# main_board.net
KiCad netlist of a schematic drawn in EAGLE
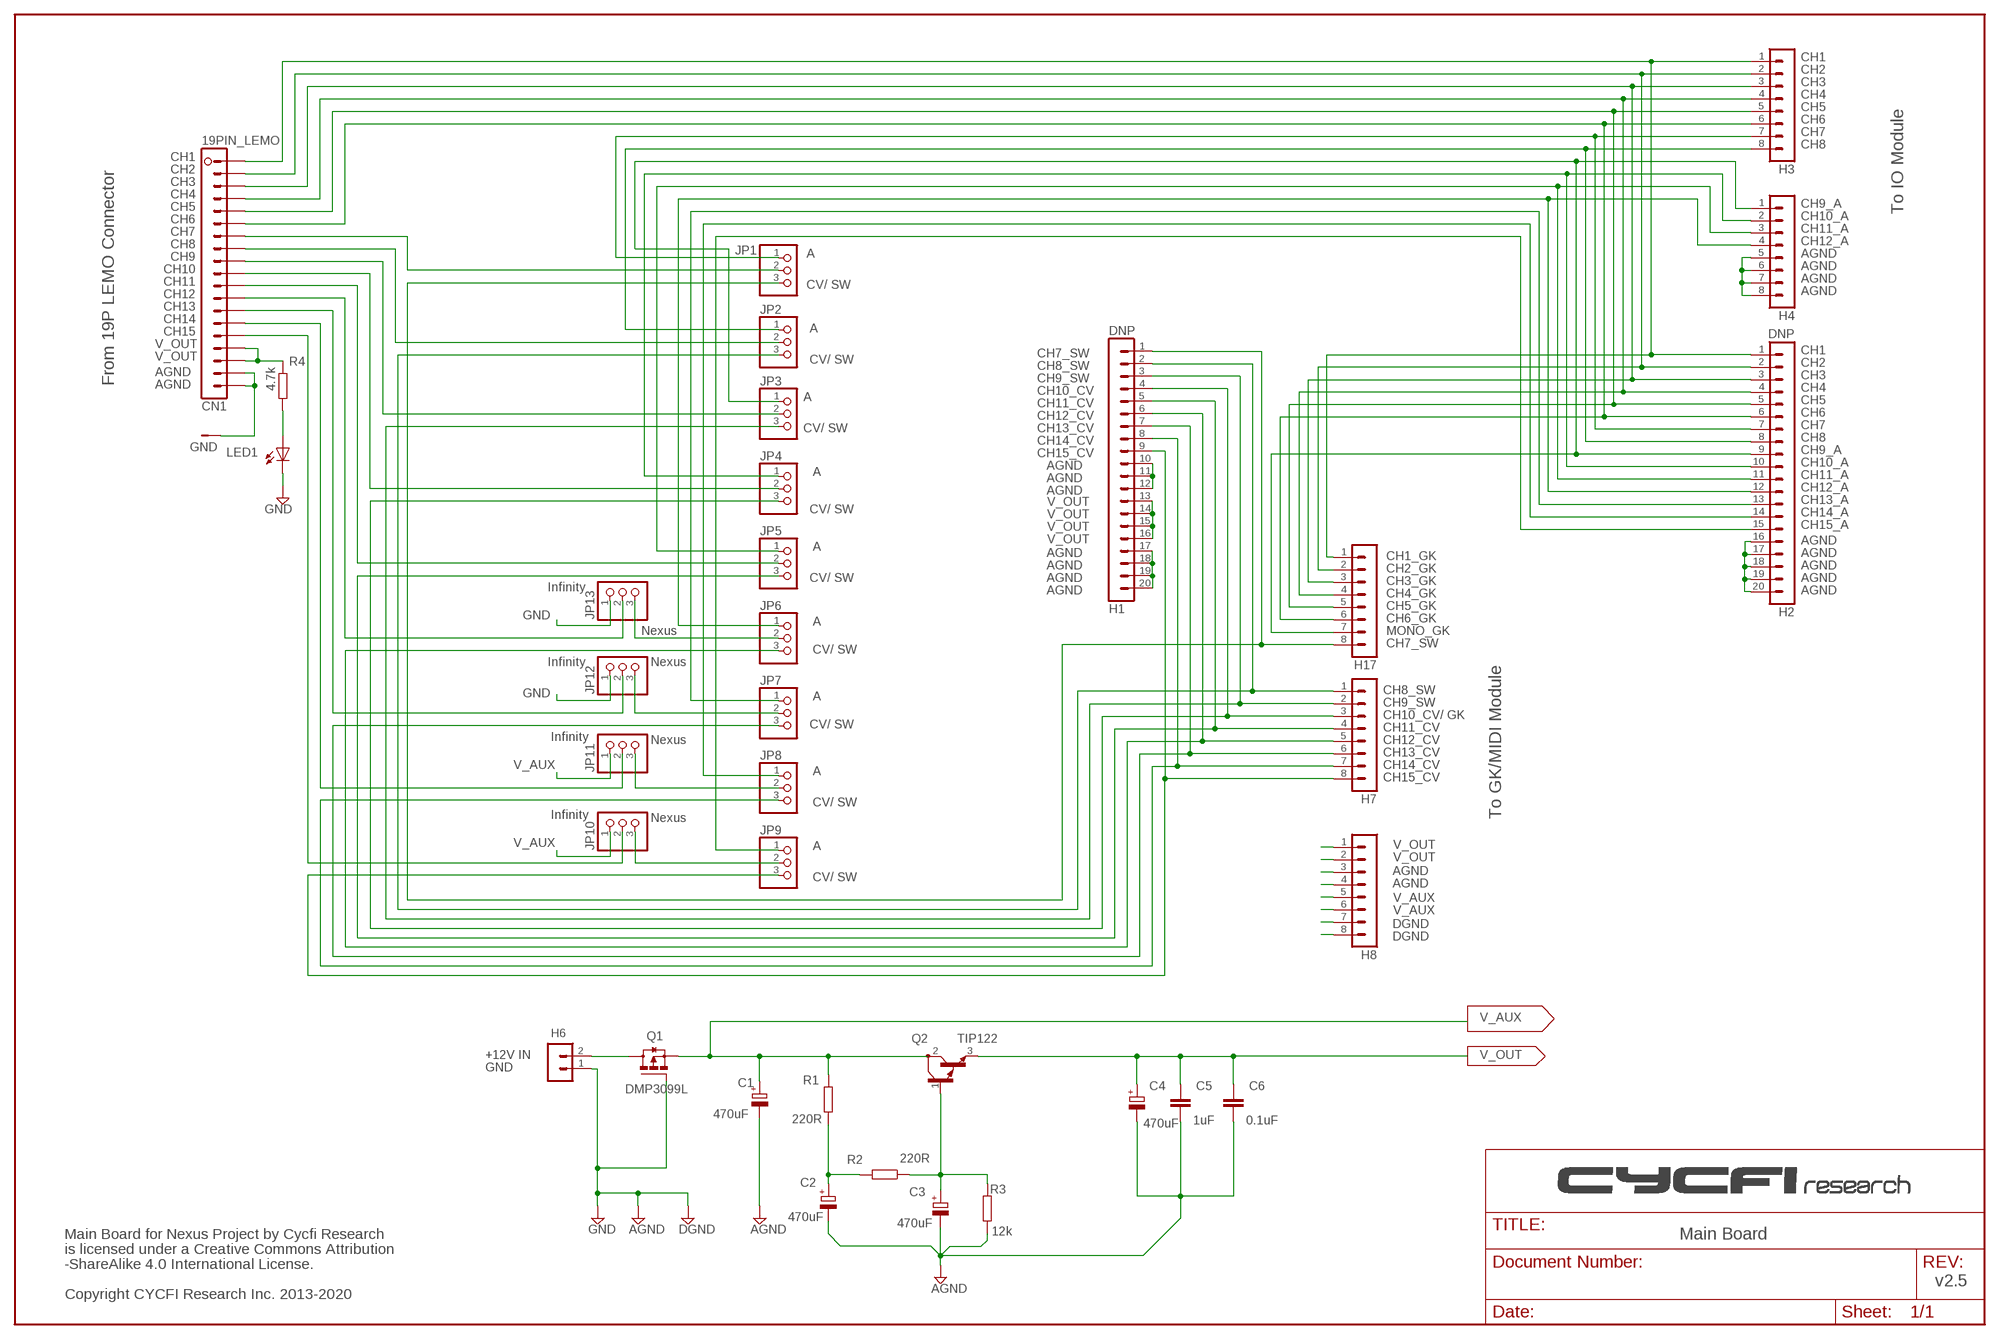
[diagram p0: schematic, sheet 1]

(export (version "E")
  (design (tool "Eeschema 10.0.6"))
  (components
    (comp (ref "C1")
      (value "470uF")
      (footprint "eagle-import:140CLH-1010")
      (libsource (lib "eagle-import") (part "CPOL-EU140CLH-1010"))
    )
    (comp (ref "C2")
      (value "470uF")
      (footprint "eagle-import:140CLH-1010")
      (libsource (lib "eagle-import") (part "CPOL-EU140CLH-1010"))
    )
    (comp (ref "C3")
      (value "470uF")
      (footprint "eagle-import:140CLH-1010")
      (libsource (lib "eagle-import") (part "CPOL-EU140CLH-1010"))
    )
    (comp (ref "C4")
      (value "470uF")
      (footprint "eagle-import:140CLH-1010")
      (libsource (lib "eagle-import") (part "CPOL-EU140CLH-1010"))
    )
    (comp (ref "C5")
      (value "1uF")
      (footprint "eagle-import:C0603")
      (libsource (lib "eagle-import") (part "C-EUC0603"))
    )
    (comp (ref "C6")
      (value "0.1uF")
      (footprint "eagle-import:C0603")
      (libsource (lib "eagle-import") (part "C-EUC0603"))
    )
    (comp (ref "CN1")
      (value "19PIN_LEMO")
      (footprint "eagle-import:19PIN_LEMO")
      (libsource (lib "eagle-import") (part "19PIN_LEMO"))
    )
    (comp (ref "GND")
      (value "TH-PAD-1.6/0.8")
      (footprint "eagle-import:TH-PAD-1.6_0.8")
      (libsource (lib "eagle-import") (part "TH-PAD-1.6/0.8"))
    )
    (comp (ref "H1")
      (value "DNP")
      (footprint "eagle-import:MA20-1")
      (libsource (lib "eagle-import") (part "MA20-1"))
    )
    (comp (ref "H2")
      (value "DNP")
      (footprint "eagle-import:MA20-1")
      (libsource (lib "eagle-import") (part "MA20-1"))
    )
    (comp (ref "H3")
      (value "MA08-1")
      (footprint "eagle-import:MA08-1")
      (libsource (lib "eagle-import") (part "MA08-1"))
    )
    (comp (ref "H4")
      (value "MA08-1")
      (footprint "eagle-import:MA08-1")
      (libsource (lib "eagle-import") (part "MA08-1"))
    )
    (comp (ref "H6")
      (value "MA02-1")
      (footprint "eagle-import:MA02-1")
      (libsource (lib "eagle-import") (part "MA02-1"))
    )
    (comp (ref "H7")
      (value "MA08-1")
      (footprint "eagle-import:MA08-1")
      (libsource (lib "eagle-import") (part "MA08-1"))
    )
    (comp (ref "H8")
      (value "MA08-1")
      (footprint "eagle-import:MA08-1")
      (libsource (lib "eagle-import") (part "MA08-1"))
    )
    (comp (ref "H17")
      (value "MA08-1")
      (footprint "eagle-import:MA08-1")
      (libsource (lib "eagle-import") (part "MA08-1"))
    )
    (comp (ref "JP1")
      (value "PINHD-1X03_2.00")
      (footprint "eagle-import:1X03M")
      (libsource (lib "eagle-import") (part "PINHD-1X03_2.00"))
    )
    (comp (ref "JP2")
      (value "PINHD-1X03_2.00")
      (footprint "eagle-import:1X03M")
      (libsource (lib "eagle-import") (part "PINHD-1X03_2.00"))
    )
    (comp (ref "JP3")
      (value "PINHD-1X03_2.00")
      (footprint "eagle-import:1X03M")
      (libsource (lib "eagle-import") (part "PINHD-1X03_2.00"))
    )
    (comp (ref "JP4")
      (value "PINHD-1X03_2.00")
      (footprint "eagle-import:1X03M")
      (libsource (lib "eagle-import") (part "PINHD-1X03_2.00"))
    )
    (comp (ref "JP5")
      (value "PINHD-1X03_2.00")
      (footprint "eagle-import:1X03M")
      (libsource (lib "eagle-import") (part "PINHD-1X03_2.00"))
    )
    (comp (ref "JP6")
      (value "PINHD-1X03_2.00")
      (footprint "eagle-import:1X03M")
      (libsource (lib "eagle-import") (part "PINHD-1X03_2.00"))
    )
    (comp (ref "JP7")
      (value "PINHD-1X03_2.00")
      (footprint "eagle-import:1X03M")
      (libsource (lib "eagle-import") (part "PINHD-1X03_2.00"))
    )
    (comp (ref "JP8")
      (value "PINHD-1X03_2.00")
      (footprint "eagle-import:1X03M")
      (libsource (lib "eagle-import") (part "PINHD-1X03_2.00"))
    )
    (comp (ref "JP9")
      (value "PINHD-1X03_2.00")
      (footprint "eagle-import:1X03M")
      (libsource (lib "eagle-import") (part "PINHD-1X03_2.00"))
    )
    (comp (ref "JP10")
      (value "PINHD-1X03_2.00")
      (footprint "eagle-import:1X03M")
      (libsource (lib "eagle-import") (part "PINHD-1X03_2.00"))
    )
    (comp (ref "JP11")
      (value "PINHD-1X03_2.00")
      (footprint "eagle-import:1X03M")
      (libsource (lib "eagle-import") (part "PINHD-1X03_2.00"))
    )
    (comp (ref "JP12")
      (value "PINHD-1X03_2.00")
      (footprint "eagle-import:1X03M")
      (libsource (lib "eagle-import") (part "PINHD-1X03_2.00"))
    )
    (comp (ref "JP13")
      (value "PINHD-1X03_2.00")
      (footprint "eagle-import:1X03M")
      (libsource (lib "eagle-import") (part "PINHD-1X03_2.00"))
    )
    (comp (ref "LED1")
      (value "LED3MM")
      (footprint "eagle-import:LED3MM")
      (libsource (lib "eagle-import") (part "LED3MM"))
    )
    (comp (ref "Q1")
      (value "DMP3099L")
      (footprint "eagle-import:SOT23")
      (libsource (lib "eagle-import") (part "P_MOSFET"))
    )
    (comp (ref "Q2")
      (value "TIP122")
      (footprint "eagle-import:TO-220H")
      (libsource (lib "eagle-import") (part "TIP122"))
    )
    (comp (ref "R1")
      (value "220R")
      (footprint "eagle-import:R0603")
      (libsource (lib "eagle-import") (part "R-EU_R0603"))
    )
    (comp (ref "R2")
      (value "220R")
      (footprint "eagle-import:R0603")
      (libsource (lib "eagle-import") (part "R-EU_R0603"))
    )
    (comp (ref "R3")
      (value "12k")
      (footprint "eagle-import:R0603")
      (libsource (lib "eagle-import") (part "R-EU_R0603"))
    )
    (comp (ref "R4")
      (value "4.7k")
      (footprint "eagle-import:R0402")
      (libsource (lib "eagle-import") (part "R-EU_R0402"))
    )
  )
  (nets
    (net (code "1") (name "/V_AUX") (class "Default")
      (node (ref "C1") (pin "+") (pinfunction "+_+") (pintype "passive"))
      (node (ref "H8") (pin "5") (pinfunction "5_5") (pintype "passive"))
      (node (ref "H8") (pin "6") (pinfunction "6_6") (pintype "passive"))
      (node (ref "JP10") (pin "1") (pinfunction "1_1") (pintype "passive"))
      (node (ref "JP11") (pin "1") (pinfunction "1_1") (pintype "passive"))
      (node (ref "Q1") (pin "2") (pinfunction "S_2") (pintype "passive"))
      (node (ref "Q2") (pin "2") (pinfunction "C_2") (pintype "passive"))
      (node (ref "R1") (pin "2") (pinfunction "2_2") (pintype "passive"))
    )
    (net (code "2") (name "/V_OUT") (class "Default")
      (node (ref "C4") (pin "+") (pinfunction "+_+") (pintype "passive"))
      (node (ref "C5") (pin "1") (pinfunction "1_1") (pintype "passive"))
      (node (ref "C6") (pin "1") (pinfunction "1_1") (pintype "passive"))
      (node (ref "CN1") (pin "P$16") (pinfunction "16_P$16") (pintype "passive"))
      (node (ref "CN1") (pin "P$17") (pinfunction "17_P$17") (pintype "passive"))
      (node (ref "H1") (pin "13") (pinfunction "13_13") (pintype "passive"))
      (node (ref "H1") (pin "14") (pinfunction "14_14") (pintype "passive"))
      (node (ref "H1") (pin "15") (pinfunction "15_15") (pintype "passive"))
      (node (ref "H1") (pin "16") (pinfunction "16_16") (pintype "passive"))
      (node (ref "H8") (pin "1") (pinfunction "1_1") (pintype "passive"))
      (node (ref "H8") (pin "2") (pinfunction "2_2") (pintype "passive"))
      (node (ref "Q2") (pin "3") (pinfunction "E_3") (pintype "passive"))
      (node (ref "R4") (pin "1") (pinfunction "1_1") (pintype "passive"))
    )
    (net (code "3") (name "AGND") (class "Default")
      (node (ref "C1") (pin "-") (pinfunction "-_-") (pintype "passive"))
      (node (ref "C2") (pin "-") (pinfunction "-_-") (pintype "passive"))
      (node (ref "C3") (pin "-") (pinfunction "-_-") (pintype "passive"))
      (node (ref "C4") (pin "-") (pinfunction "-_-") (pintype "passive"))
      (node (ref "C5") (pin "2") (pinfunction "2_2") (pintype "passive"))
      (node (ref "C6") (pin "2") (pinfunction "2_2") (pintype "passive"))
      (node (ref "CN1") (pin "P$18") (pinfunction "18_P$18") (pintype "passive"))
      (node (ref "CN1") (pin "P$19") (pinfunction "19_P$19") (pintype "passive"))
      (node (ref "GND") (pin "1") (pinfunction "P_1") (pintype "passive"))
      (node (ref "H1") (pin "10") (pinfunction "10_10") (pintype "passive"))
      (node (ref "H1") (pin "11") (pinfunction "11_11") (pintype "passive"))
      (node (ref "H1") (pin "12") (pinfunction "12_12") (pintype "passive"))
      (node (ref "H1") (pin "17") (pinfunction "17_17") (pintype "passive"))
      (node (ref "H1") (pin "18") (pinfunction "18_18") (pintype "passive"))
      (node (ref "H1") (pin "19") (pinfunction "19_19") (pintype "passive"))
      (node (ref "H1") (pin "20") (pinfunction "20_20") (pintype "passive"))
      (node (ref "H2") (pin "16") (pinfunction "16_16") (pintype "passive"))
      (node (ref "H2") (pin "17") (pinfunction "17_17") (pintype "passive"))
      (node (ref "H2") (pin "18") (pinfunction "18_18") (pintype "passive"))
      (node (ref "H2") (pin "19") (pinfunction "19_19") (pintype "passive"))
      (node (ref "H2") (pin "20") (pinfunction "20_20") (pintype "passive"))
      (node (ref "H4") (pin "5") (pinfunction "5_5") (pintype "passive"))
      (node (ref "H4") (pin "6") (pinfunction "6_6") (pintype "passive"))
      (node (ref "H4") (pin "7") (pinfunction "7_7") (pintype "passive"))
      (node (ref "H4") (pin "8") (pinfunction "8_8") (pintype "passive"))
      (node (ref "H6") (pin "1") (pinfunction "1_1") (pintype "passive"))
      (node (ref "H8") (pin "3") (pinfunction "3_3") (pintype "passive"))
      (node (ref "H8") (pin "4") (pinfunction "4_4") (pintype "passive"))
      (node (ref "H8") (pin "7") (pinfunction "7_7") (pintype "passive"))
      (node (ref "H8") (pin "8") (pinfunction "8_8") (pintype "passive"))
      (node (ref "JP12") (pin "1") (pinfunction "1_1") (pintype "passive"))
      (node (ref "JP13") (pin "1") (pinfunction "1_1") (pintype "passive"))
      (node (ref "LED1") (pin "K") (pinfunction "C_K") (pintype "passive"))
      (node (ref "Q1") (pin "1") (pinfunction "G_1") (pintype "passive"))
      (node (ref "R3") (pin "1") (pinfunction "1_1") (pintype "passive"))
    )
    (net (code "4") (name "Net-(C2-Pad+)") (class "Default")
      (node (ref "C2") (pin "+") (pinfunction "+_+") (pintype "passive"))
      (node (ref "R1") (pin "1") (pinfunction "1_1") (pintype "passive"))
      (node (ref "R2") (pin "2") (pinfunction "2_2") (pintype "passive"))
    )
    (net (code "5") (name "Net-(CN1-1)") (class "Default")
      (node (ref "CN1") (pin "P$1") (pinfunction "1_P$1") (pintype "passive"))
      (node (ref "H17") (pin "1") (pinfunction "1_1") (pintype "passive"))
      (node (ref "H2") (pin "1") (pinfunction "1_1") (pintype "passive"))
      (node (ref "H3") (pin "1") (pinfunction "1_1") (pintype "passive"))
    )
    (net (code "6") (name "Net-(CN1-2)") (class "Default")
      (node (ref "CN1") (pin "P$2") (pinfunction "2_P$2") (pintype "passive"))
      (node (ref "H17") (pin "2") (pinfunction "2_2") (pintype "passive"))
      (node (ref "H2") (pin "2") (pinfunction "2_2") (pintype "passive"))
      (node (ref "H3") (pin "2") (pinfunction "2_2") (pintype "passive"))
    )
    (net (code "7") (name "Net-(CN1-3)") (class "Default")
      (node (ref "CN1") (pin "P$3") (pinfunction "3_P$3") (pintype "passive"))
      (node (ref "H17") (pin "3") (pinfunction "3_3") (pintype "passive"))
      (node (ref "H2") (pin "3") (pinfunction "3_3") (pintype "passive"))
      (node (ref "H3") (pin "3") (pinfunction "3_3") (pintype "passive"))
    )
    (net (code "8") (name "Net-(CN1-4)") (class "Default")
      (node (ref "CN1") (pin "P$4") (pinfunction "4_P$4") (pintype "passive"))
      (node (ref "H17") (pin "4") (pinfunction "4_4") (pintype "passive"))
      (node (ref "H2") (pin "4") (pinfunction "4_4") (pintype "passive"))
      (node (ref "H3") (pin "4") (pinfunction "4_4") (pintype "passive"))
    )
    (net (code "9") (name "Net-(CN1-5)") (class "Default")
      (node (ref "CN1") (pin "P$5") (pinfunction "5_P$5") (pintype "passive"))
      (node (ref "H17") (pin "5") (pinfunction "5_5") (pintype "passive"))
      (node (ref "H2") (pin "5") (pinfunction "5_5") (pintype "passive"))
      (node (ref "H3") (pin "5") (pinfunction "5_5") (pintype "passive"))
    )
    (net (code "10") (name "Net-(CN1-6)") (class "Default")
      (node (ref "CN1") (pin "P$6") (pinfunction "6_P$6") (pintype "passive"))
      (node (ref "H17") (pin "6") (pinfunction "6_6") (pintype "passive"))
      (node (ref "H2") (pin "6") (pinfunction "6_6") (pintype "passive"))
      (node (ref "H3") (pin "6") (pinfunction "6_6") (pintype "passive"))
    )
    (net (code "11") (name "Net-(CN1-7)") (class "Default")
      (node (ref "CN1") (pin "P$7") (pinfunction "7_P$7") (pintype "passive"))
      (node (ref "JP1") (pin "2") (pinfunction "2_2") (pintype "passive"))
    )
    (net (code "12") (name "Net-(CN1-8)") (class "Default")
      (node (ref "CN1") (pin "P$8") (pinfunction "8_P$8") (pintype "passive"))
      (node (ref "JP2") (pin "2") (pinfunction "2_2") (pintype "passive"))
    )
    (net (code "13") (name "Net-(CN1-9)") (class "Default")
      (node (ref "CN1") (pin "P$9") (pinfunction "9_P$9") (pintype "passive"))
      (node (ref "JP3") (pin "2") (pinfunction "2_2") (pintype "passive"))
    )
    (net (code "14") (name "Net-(CN1-10)") (class "Default")
      (node (ref "CN1") (pin "P$10") (pinfunction "10_P$10") (pintype "passive"))
      (node (ref "JP4") (pin "2") (pinfunction "2_2") (pintype "passive"))
    )
    (net (code "15") (name "Net-(CN1-11)") (class "Default")
      (node (ref "CN1") (pin "P$11") (pinfunction "11_P$11") (pintype "passive"))
      (node (ref "JP5") (pin "2") (pinfunction "2_2") (pintype "passive"))
    )
    (net (code "16") (name "Net-(CN1-12)") (class "Default")
      (node (ref "CN1") (pin "P$12") (pinfunction "12_P$12") (pintype "passive"))
      (node (ref "JP13") (pin "2") (pinfunction "2_2") (pintype "passive"))
    )
    (net (code "17") (name "Net-(CN1-13)") (class "Default")
      (node (ref "CN1") (pin "P$13") (pinfunction "13_P$13") (pintype "passive"))
      (node (ref "JP12") (pin "2") (pinfunction "2_2") (pintype "passive"))
    )
    (net (code "18") (name "Net-(CN1-14)") (class "Default")
      (node (ref "CN1") (pin "P$14") (pinfunction "14_P$14") (pintype "passive"))
      (node (ref "JP11") (pin "2") (pinfunction "2_2") (pintype "passive"))
    )
    (net (code "19") (name "Net-(CN1-15)") (class "Default")
      (node (ref "CN1") (pin "P$15") (pinfunction "15_P$15") (pintype "passive"))
      (node (ref "JP10") (pin "2") (pinfunction "2_2") (pintype "passive"))
    )
    (net (code "20") (name "Net-(H1-Pad1)") (class "Default")
      (node (ref "H1") (pin "1") (pinfunction "1_1") (pintype "passive"))
      (node (ref "H17") (pin "8") (pinfunction "8_8") (pintype "passive"))
      (node (ref "JP1") (pin "3") (pinfunction "3_3") (pintype "passive"))
    )
    (net (code "21") (name "Net-(H1-Pad2)") (class "Default")
      (node (ref "H1") (pin "2") (pinfunction "2_2") (pintype "passive"))
      (node (ref "H7") (pin "1") (pinfunction "1_1") (pintype "passive"))
      (node (ref "JP2") (pin "3") (pinfunction "3_3") (pintype "passive"))
    )
    (net (code "22") (name "Net-(H1-Pad3)") (class "Default")
      (node (ref "H1") (pin "3") (pinfunction "3_3") (pintype "passive"))
      (node (ref "H7") (pin "2") (pinfunction "2_2") (pintype "passive"))
      (node (ref "JP3") (pin "3") (pinfunction "3_3") (pintype "passive"))
    )
    (net (code "23") (name "Net-(H1-Pad4)") (class "Default")
      (node (ref "H1") (pin "4") (pinfunction "4_4") (pintype "passive"))
      (node (ref "H7") (pin "3") (pinfunction "3_3") (pintype "passive"))
      (node (ref "JP4") (pin "3") (pinfunction "3_3") (pintype "passive"))
    )
    (net (code "24") (name "Net-(H1-Pad5)") (class "Default")
      (node (ref "H1") (pin "5") (pinfunction "5_5") (pintype "passive"))
      (node (ref "H7") (pin "4") (pinfunction "4_4") (pintype "passive"))
      (node (ref "JP5") (pin "3") (pinfunction "3_3") (pintype "passive"))
    )
    (net (code "25") (name "Net-(H1-Pad6)") (class "Default")
      (node (ref "H1") (pin "6") (pinfunction "6_6") (pintype "passive"))
      (node (ref "H7") (pin "5") (pinfunction "5_5") (pintype "passive"))
      (node (ref "JP6") (pin "3") (pinfunction "3_3") (pintype "passive"))
    )
    (net (code "26") (name "Net-(H1-Pad7)") (class "Default")
      (node (ref "H1") (pin "7") (pinfunction "7_7") (pintype "passive"))
      (node (ref "H7") (pin "6") (pinfunction "6_6") (pintype "passive"))
      (node (ref "JP7") (pin "3") (pinfunction "3_3") (pintype "passive"))
    )
    (net (code "27") (name "Net-(H1-Pad8)") (class "Default")
      (node (ref "H1") (pin "8") (pinfunction "8_8") (pintype "passive"))
      (node (ref "H7") (pin "7") (pinfunction "7_7") (pintype "passive"))
      (node (ref "JP8") (pin "3") (pinfunction "3_3") (pintype "passive"))
    )
    (net (code "28") (name "Net-(H1-Pad9)") (class "Default")
      (node (ref "H1") (pin "9") (pinfunction "9_9") (pintype "passive"))
      (node (ref "H7") (pin "8") (pinfunction "8_8") (pintype "passive"))
      (node (ref "JP9") (pin "3") (pinfunction "3_3") (pintype "passive"))
    )
    (net (code "29") (name "Net-(H2-Pad7)") (class "Default")
      (node (ref "H2") (pin "7") (pinfunction "7_7") (pintype "passive"))
      (node (ref "H3") (pin "7") (pinfunction "7_7") (pintype "passive"))
      (node (ref "JP1") (pin "1") (pinfunction "1_1") (pintype "passive"))
    )
    (net (code "30") (name "Net-(H2-Pad8)") (class "Default")
      (node (ref "H2") (pin "8") (pinfunction "8_8") (pintype "passive"))
      (node (ref "H3") (pin "8") (pinfunction "8_8") (pintype "passive"))
      (node (ref "JP2") (pin "1") (pinfunction "1_1") (pintype "passive"))
    )
    (net (code "31") (name "Net-(H2-Pad10)") (class "Default")
      (node (ref "H2") (pin "10") (pinfunction "10_10") (pintype "passive"))
      (node (ref "H4") (pin "2") (pinfunction "2_2") (pintype "passive"))
      (node (ref "JP4") (pin "1") (pinfunction "1_1") (pintype "passive"))
    )
    (net (code "32") (name "Net-(H2-Pad11)") (class "Default")
      (node (ref "H2") (pin "11") (pinfunction "11_11") (pintype "passive"))
      (node (ref "H4") (pin "3") (pinfunction "3_3") (pintype "passive"))
      (node (ref "JP5") (pin "1") (pinfunction "1_1") (pintype "passive"))
    )
    (net (code "33") (name "Net-(H2-Pad12)") (class "Default")
      (node (ref "H2") (pin "12") (pinfunction "12_12") (pintype "passive"))
      (node (ref "H4") (pin "4") (pinfunction "4_4") (pintype "passive"))
      (node (ref "JP6") (pin "1") (pinfunction "1_1") (pintype "passive"))
    )
    (net (code "34") (name "Net-(H2-Pad13)") (class "Default")
      (node (ref "H2") (pin "13") (pinfunction "13_13") (pintype "passive"))
      (node (ref "JP7") (pin "1") (pinfunction "1_1") (pintype "passive"))
    )
    (net (code "35") (name "Net-(H2-Pad14)") (class "Default")
      (node (ref "H2") (pin "14") (pinfunction "14_14") (pintype "passive"))
      (node (ref "JP8") (pin "1") (pinfunction "1_1") (pintype "passive"))
    )
    (net (code "36") (name "Net-(H2-Pad15)") (class "Default")
      (node (ref "H2") (pin "15") (pinfunction "15_15") (pintype "passive"))
      (node (ref "JP9") (pin "1") (pinfunction "1_1") (pintype "passive"))
    )
    (net (code "37") (name "Net-(H17-Pad7)") (class "Default")
      (node (ref "H17") (pin "7") (pinfunction "7_7") (pintype "passive"))
      (node (ref "H2") (pin "9") (pinfunction "9_9") (pintype "passive"))
      (node (ref "H4") (pin "1") (pinfunction "1_1") (pintype "passive"))
      (node (ref "JP3") (pin "1") (pinfunction "1_1") (pintype "passive"))
    )
    (net (code "38") (name "Net-(JP10-Pad3)") (class "Default")
      (node (ref "JP10") (pin "3") (pinfunction "3_3") (pintype "passive"))
      (node (ref "JP9") (pin "2") (pinfunction "2_2") (pintype "passive"))
    )
    (net (code "39") (name "Net-(JP11-Pad3)") (class "Default")
      (node (ref "JP11") (pin "3") (pinfunction "3_3") (pintype "passive"))
      (node (ref "JP8") (pin "2") (pinfunction "2_2") (pintype "passive"))
    )
    (net (code "40") (name "Net-(JP12-Pad3)") (class "Default")
      (node (ref "JP12") (pin "3") (pinfunction "3_3") (pintype "passive"))
      (node (ref "JP7") (pin "2") (pinfunction "2_2") (pintype "passive"))
    )
    (net (code "41") (name "Net-(JP13-Pad3)") (class "Default")
      (node (ref "JP13") (pin "3") (pinfunction "3_3") (pintype "passive"))
      (node (ref "JP6") (pin "2") (pinfunction "2_2") (pintype "passive"))
    )
    (net (code "42") (name "Net-(LED1-PadA)") (class "Default")
      (node (ref "LED1") (pin "A") (pinfunction "A_A") (pintype "passive"))
      (node (ref "R4") (pin "2") (pinfunction "2_2") (pintype "passive"))
    )
    (net (code "43") (name "Net-(Q1-D)") (class "Default")
      (node (ref "H6") (pin "2") (pinfunction "2_2") (pintype "passive"))
      (node (ref "Q1") (pin "3") (pinfunction "D_3") (pintype "passive"))
    )
    (net (code "44") (name "Net-(Q2-B)") (class "Default")
      (node (ref "C3") (pin "+") (pinfunction "+_+") (pintype "passive"))
      (node (ref "Q2") (pin "1") (pinfunction "B_1") (pintype "passive"))
      (node (ref "R2") (pin "1") (pinfunction "1_1") (pintype "passive"))
      (node (ref "R3") (pin "2") (pinfunction "2_2") (pintype "passive"))
    )
  )
)
